# SPv1.net
KiCad netlist of a schematic drawn in EAGLE
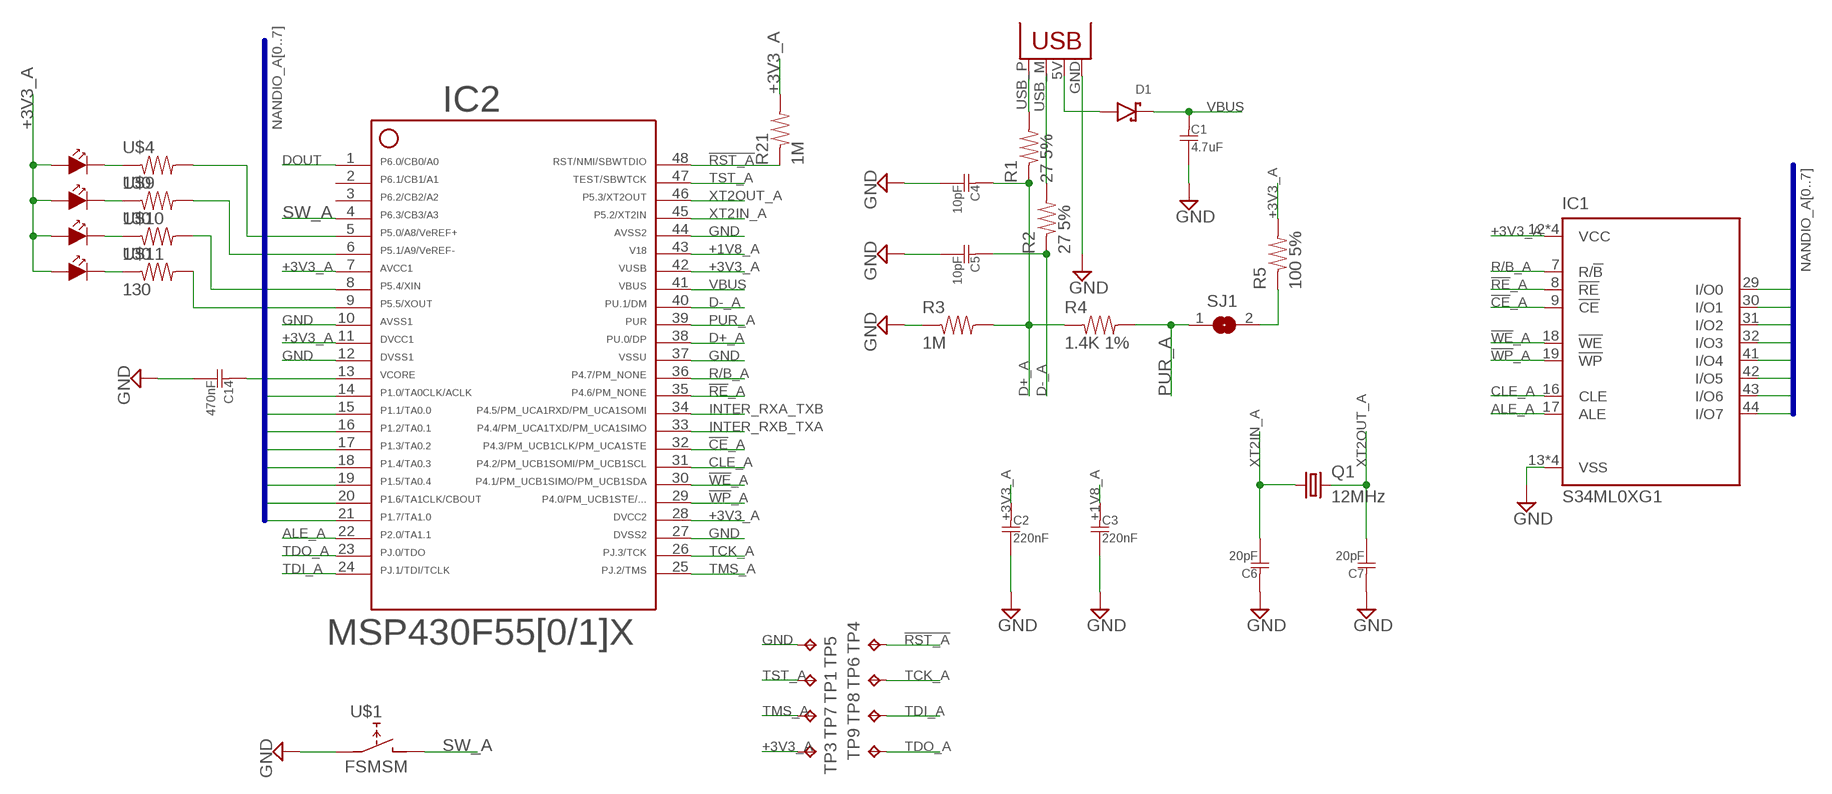
[diagram p0: schematic, sheet 1]
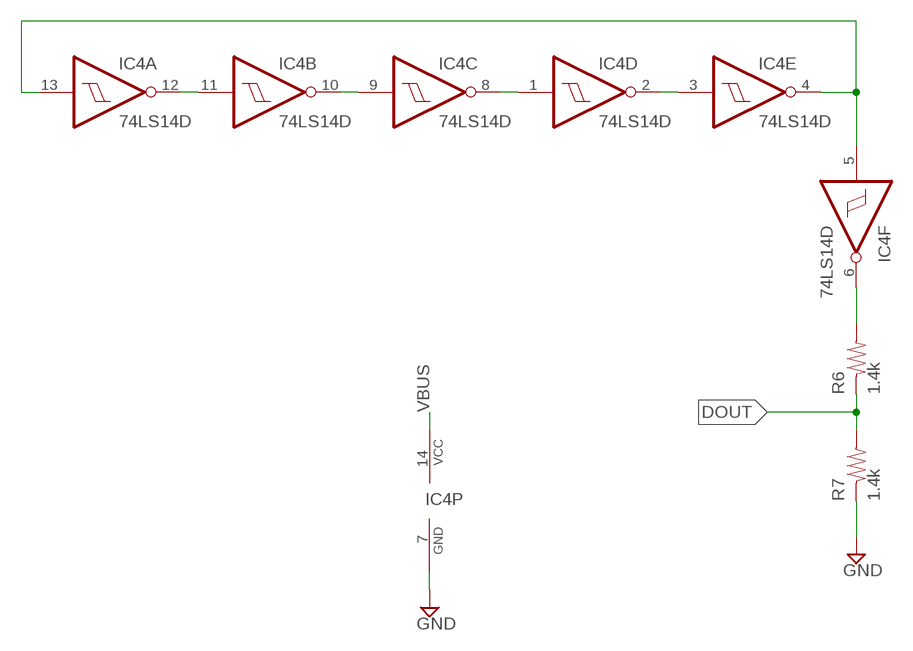
[diagram p1: schematic, sheet 2]
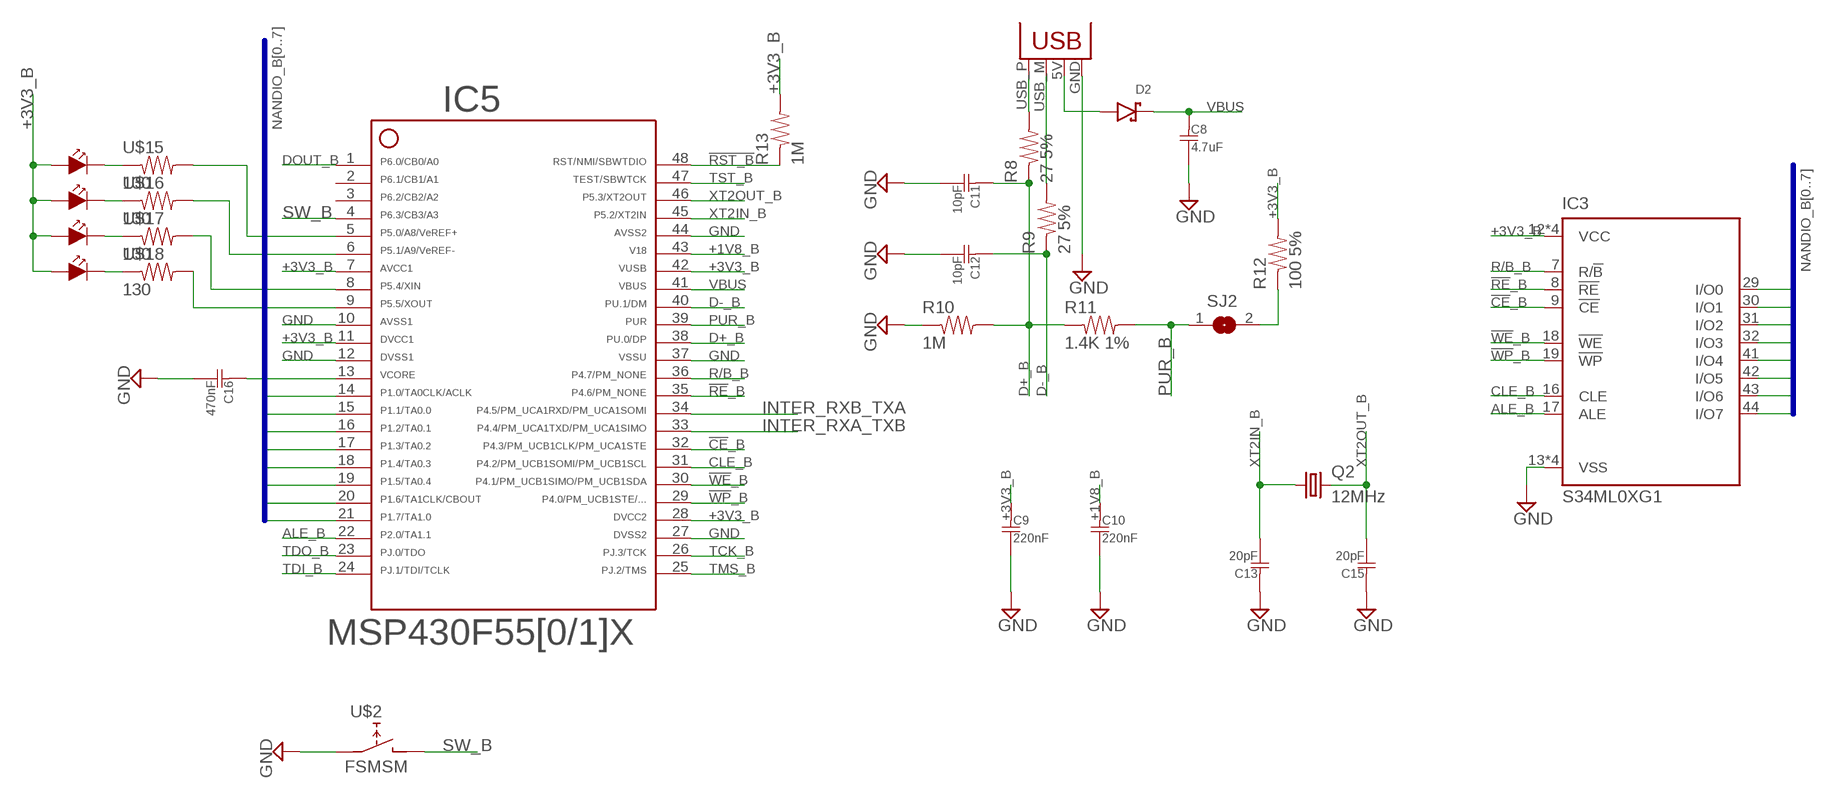
[diagram p2: schematic, sheet 3]
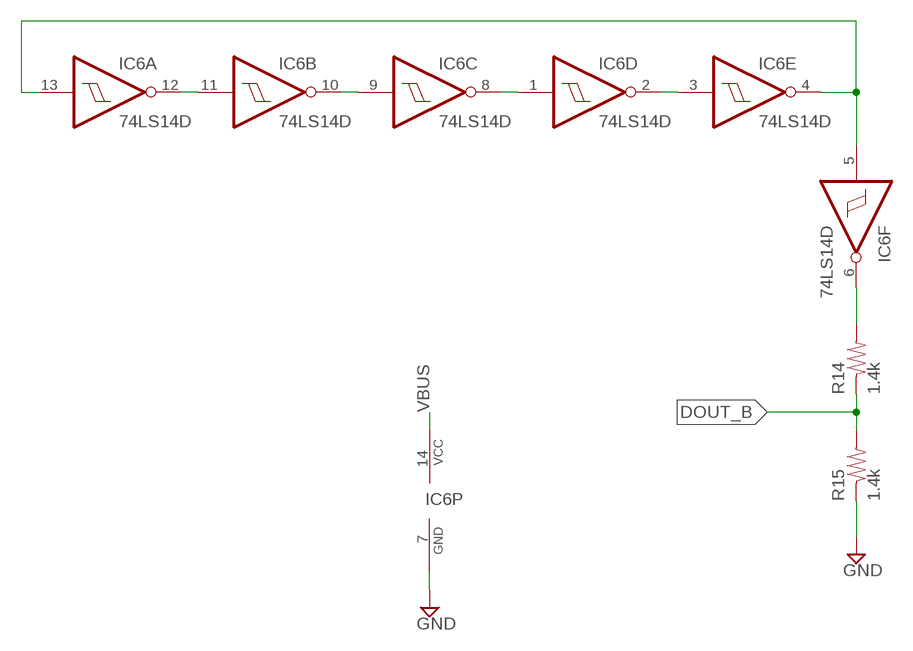
[diagram p3: schematic, sheet 4]

(export (version "E")
  (design (tool "Eeschema 10.0.6"))
  (components
    (comp (ref "IC4")
      (value "74LS14D")
      (footprint "eagle-import:SO14")
      (libsource (lib "eagle-import") (part "7414DLS"))
    )
    (comp (ref "R6")
      (value "1.4k")
      (footprint "eagle-import:R0805")
      (libsource (lib "eagle-import") (part "R0805"))
    )
    (comp (ref "R7")
      (value "1.4k")
      (footprint "eagle-import:R0805")
      (libsource (lib "eagle-import") (part "R0805"))
    )
    (comp (ref "C1")
      (value "4.7uF")
      (footprint "eagle-import:R0805")
      (libsource (lib "eagle-import") (part "C0805"))
    )
    (comp (ref "C2")
      (value "220nF")
      (footprint "eagle-import:R0805")
      (libsource (lib "eagle-import") (part "C0805"))
    )
    (comp (ref "C3")
      (value "220nF")
      (footprint "eagle-import:R0805")
      (libsource (lib "eagle-import") (part "C0805"))
    )
    (comp (ref "C4")
      (value "10pF")
      (footprint "eagle-import:R0805")
      (libsource (lib "eagle-import") (part "C0805"))
    )
    (comp (ref "C5")
      (value "10pF")
      (footprint "eagle-import:R0805")
      (libsource (lib "eagle-import") (part "C0805"))
    )
    (comp (ref "C6")
      (value "20pF")
      (footprint "eagle-import:R0805")
      (libsource (lib "eagle-import") (part "C0805"))
    )
    (comp (ref "C7")
      (value "20pF")
      (footprint "eagle-import:R0805")
      (libsource (lib "eagle-import") (part "C0805"))
    )
    (comp (ref "C14")
      (value "470nF")
      (footprint "eagle-import:R0805")
      (libsource (lib "eagle-import") (part "C0805"))
    )
    (comp (ref "D1")
      (value "D-SCHOTTKY")
      (footprint "eagle-import:SOD123")
      (libsource (lib "eagle-import") (part "D-SCHOTTKY"))
    )
    (comp (ref "IC1")
      (value "S34ML0XG1")
      (footprint "eagle-import:TSOP48")
      (libsource (lib "eagle-import") (part "S34ML0XG1"))
    )
    (comp (ref "IC2")
      (value "F55[0/1]X---PT48")
      (footprint "eagle-import:PT48")
      (libsource (lib "eagle-import") (part "F55[0/1]X---PT48"))
    )
    (comp (ref "JP1")
      (value "USBPCB")
      (footprint "eagle-import:USB-A-PCB")
      (libsource (lib "eagle-import") (part "USBPCB"))
    )
    (comp (ref "Q1")
      (value "12MHz")
      (footprint "eagle-import:CSM-3X")
      (libsource (lib "eagle-import") (part "CRYSTALCSM-3X"))
    )
    (comp (ref "R1")
      (value "27 5%")
      (footprint "eagle-import:R0805")
      (libsource (lib "eagle-import") (part "R0805"))
    )
    (comp (ref "R2")
      (value "27 5%")
      (footprint "eagle-import:R0805")
      (libsource (lib "eagle-import") (part "R0805"))
    )
    (comp (ref "R3")
      (value "1M")
      (footprint "eagle-import:R0805")
      (libsource (lib "eagle-import") (part "R0805"))
    )
    (comp (ref "R4")
      (value "1.4K 1%")
      (footprint "eagle-import:R0805")
      (libsource (lib "eagle-import") (part "R0805"))
    )
    (comp (ref "R5")
      (value "100 5%")
      (footprint "eagle-import:R0805")
      (libsource (lib "eagle-import") (part "R0805"))
    )
    (comp (ref "R21")
      (value "1M")
      (footprint "eagle-import:R0805")
      (libsource (lib "eagle-import") (part "R0805"))
    )
    (comp (ref "SJ1")
      (value "SJW")
      (footprint "eagle-import:SJW")
      (libsource (lib "eagle-import") (part "SJW"))
    )
    (comp (ref "TP1")
      (value "TPTP08SQ")
      (footprint "eagle-import:TP08SQ")
      (libsource (lib "eagle-import") (part "TPTP08SQ"))
    )
    (comp (ref "TP3")
      (value "TPTP08SQ")
      (footprint "eagle-import:TP08SQ")
      (libsource (lib "eagle-import") (part "TPTP08SQ"))
    )
    (comp (ref "TP4")
      (value "TPTP08SQ")
      (footprint "eagle-import:TP08SQ")
      (libsource (lib "eagle-import") (part "TPTP08SQ"))
    )
    (comp (ref "TP5")
      (value "TPTP08SQ")
      (footprint "eagle-import:TP08SQ")
      (libsource (lib "eagle-import") (part "TPTP08SQ"))
    )
    (comp (ref "TP6")
      (value "TPTP08SQ")
      (footprint "eagle-import:TP08SQ")
      (libsource (lib "eagle-import") (part "TPTP08SQ"))
    )
    (comp (ref "TP7")
      (value "TPTP08SQ")
      (footprint "eagle-import:TP08SQ")
      (libsource (lib "eagle-import") (part "TPTP08SQ"))
    )
    (comp (ref "TP8")
      (value "TPTP08SQ")
      (footprint "eagle-import:TP08SQ")
      (libsource (lib "eagle-import") (part "TPTP08SQ"))
    )
    (comp (ref "TP9")
      (value "TPTP08SQ")
      (footprint "eagle-import:TP08SQ")
      (libsource (lib "eagle-import") (part "TPTP08SQ"))
    )
    (comp (ref "U$1")
      (value "FSMSM")
      (footprint "eagle-import:FSMSM")
      (libsource (lib "eagle-import") (part "FSMSM"))
    )
    (comp (ref "U$4")
      (value "130")
      (footprint "eagle-import:R0805")
      (libsource (lib "eagle-import") (part "R0805"))
    )
    (comp (ref "U$5")
      (value "LED")
      (footprint "eagle-import:LED0805")
      (libsource (lib "eagle-import") (part "LED"))
    )
    (comp (ref "U$6")
      (value "LED")
      (footprint "eagle-import:LED0805")
      (libsource (lib "eagle-import") (part "LED"))
    )
    (comp (ref "U$7")
      (value "LED")
      (footprint "eagle-import:LED0805")
      (libsource (lib "eagle-import") (part "LED"))
    )
    (comp (ref "U$8")
      (value "LED")
      (footprint "eagle-import:LED0805")
      (libsource (lib "eagle-import") (part "LED"))
    )
    (comp (ref "U$9")
      (value "130")
      (footprint "eagle-import:R0805")
      (libsource (lib "eagle-import") (part "R0805"))
    )
    (comp (ref "U$10")
      (value "130")
      (footprint "eagle-import:R0805")
      (libsource (lib "eagle-import") (part "R0805"))
    )
    (comp (ref "U$11")
      (value "130")
      (footprint "eagle-import:R0805")
      (libsource (lib "eagle-import") (part "R0805"))
    )
    (comp (ref "C8")
      (value "4.7uF")
      (footprint "eagle-import:R0805")
      (libsource (lib "eagle-import") (part "C0805"))
    )
    (comp (ref "C9")
      (value "220nF")
      (footprint "eagle-import:R0805")
      (libsource (lib "eagle-import") (part "C0805"))
    )
    (comp (ref "C10")
      (value "220nF")
      (footprint "eagle-import:R0805")
      (libsource (lib "eagle-import") (part "C0805"))
    )
    (comp (ref "C11")
      (value "10pF")
      (footprint "eagle-import:R0805")
      (libsource (lib "eagle-import") (part "C0805"))
    )
    (comp (ref "C12")
      (value "10pF")
      (footprint "eagle-import:R0805")
      (libsource (lib "eagle-import") (part "C0805"))
    )
    (comp (ref "C13")
      (value "20pF")
      (footprint "eagle-import:R0805")
      (libsource (lib "eagle-import") (part "C0805"))
    )
    (comp (ref "C15")
      (value "20pF")
      (footprint "eagle-import:R0805")
      (libsource (lib "eagle-import") (part "C0805"))
    )
    (comp (ref "C16")
      (value "470nF")
      (footprint "eagle-import:R0805")
      (libsource (lib "eagle-import") (part "C0805"))
    )
    (comp (ref "D2")
      (value "D-SCHOTTKY")
      (footprint "eagle-import:SOD123")
      (libsource (lib "eagle-import") (part "D-SCHOTTKY"))
    )
    (comp (ref "IC3")
      (value "S34ML0XG1")
      (footprint "eagle-import:TSOP48")
      (libsource (lib "eagle-import") (part "S34ML0XG1"))
    )
    (comp (ref "IC5")
      (value "F55[0/1]X---PT48")
      (footprint "eagle-import:PT48")
      (libsource (lib "eagle-import") (part "F55[0/1]X---PT48"))
    )
    (comp (ref "JP2")
      (value "USBPCB")
      (footprint "eagle-import:USB-A-PCB")
      (libsource (lib "eagle-import") (part "USBPCB"))
    )
    (comp (ref "Q2")
      (value "12MHz")
      (footprint "eagle-import:CSM-3X")
      (libsource (lib "eagle-import") (part "CRYSTALCSM-3X"))
    )
    (comp (ref "R8")
      (value "27 5%")
      (footprint "eagle-import:R0805")
      (libsource (lib "eagle-import") (part "R0805"))
    )
    (comp (ref "R9")
      (value "27 5%")
      (footprint "eagle-import:R0805")
      (libsource (lib "eagle-import") (part "R0805"))
    )
    (comp (ref "R10")
      (value "1M")
      (footprint "eagle-import:R0805")
      (libsource (lib "eagle-import") (part "R0805"))
    )
    (comp (ref "R11")
      (value "1.4K 1%")
      (footprint "eagle-import:R0805")
      (libsource (lib "eagle-import") (part "R0805"))
    )
    (comp (ref "R12")
      (value "100 5%")
      (footprint "eagle-import:R0805")
      (libsource (lib "eagle-import") (part "R0805"))
    )
    (comp (ref "R13")
      (value "1M")
      (footprint "eagle-import:R0805")
      (libsource (lib "eagle-import") (part "R0805"))
    )
    (comp (ref "SJ2")
      (value "SJW")
      (footprint "eagle-import:SJW")
      (libsource (lib "eagle-import") (part "SJW"))
    )
    (comp (ref "U$2")
      (value "FSMSM")
      (footprint "eagle-import:FSMSM")
      (libsource (lib "eagle-import") (part "FSMSM"))
    )
    (comp (ref "U$3")
      (value "LED")
      (footprint "eagle-import:LED0805")
      (libsource (lib "eagle-import") (part "LED"))
    )
    (comp (ref "U$12")
      (value "LED")
      (footprint "eagle-import:LED0805")
      (libsource (lib "eagle-import") (part "LED"))
    )
    (comp (ref "U$13")
      (value "LED")
      (footprint "eagle-import:LED0805")
      (libsource (lib "eagle-import") (part "LED"))
    )
    (comp (ref "U$14")
      (value "LED")
      (footprint "eagle-import:LED0805")
      (libsource (lib "eagle-import") (part "LED"))
    )
    (comp (ref "U$15")
      (value "130")
      (footprint "eagle-import:R0805")
      (libsource (lib "eagle-import") (part "R0805"))
    )
    (comp (ref "U$16")
      (value "130")
      (footprint "eagle-import:R0805")
      (libsource (lib "eagle-import") (part "R0805"))
    )
    (comp (ref "U$17")
      (value "130")
      (footprint "eagle-import:R0805")
      (libsource (lib "eagle-import") (part "R0805"))
    )
    (comp (ref "U$18")
      (value "130")
      (footprint "eagle-import:R0805")
      (libsource (lib "eagle-import") (part "R0805"))
    )
    (comp (ref "IC6")
      (value "74LS14D")
      (footprint "eagle-import:SO14")
      (libsource (lib "eagle-import") (part "7414DLS"))
    )
    (comp (ref "R14")
      (value "1.4k")
      (footprint "eagle-import:R0805")
      (libsource (lib "eagle-import") (part "R0805"))
    )
    (comp (ref "R15")
      (value "1.4k")
      (footprint "eagle-import:R0805")
      (libsource (lib "eagle-import") (part "R0805"))
    )
  )
  (nets
    (net (code "9") (name "+1V8_A") (class "Default")
      (node (ref "C3") (pin "P$1") (pinfunction "1_P$1") (pintype "passive"))
      (node (ref "IC2") (pin "43") (pinfunction "43_43") (pintype "power_in"))
    )
    (net (code "10") (name "+1V8_B") (class "Default")
      (node (ref "C10") (pin "P$1") (pinfunction "1_P$1") (pintype "passive"))
      (node (ref "IC5") (pin "43") (pinfunction "43_43") (pintype "power_in"))
    )
    (net (code "11") (name "+3V3_A") (class "Default")
      (node (ref "C2") (pin "P$1") (pinfunction "1_P$1") (pintype "passive"))
      (node (ref "IC1") (pin "12") (pinfunction "VCC_12") (pintype "power_in"))
      (node (ref "IC1") (pin "34") (pinfunction "VCC_34") (pintype "power_in"))
      (node (ref "IC1") (pin "37") (pinfunction "VCC_37") (pintype "power_in"))
      (node (ref "IC1") (pin "39") (pinfunction "VCC_39") (pintype "power_in"))
      (node (ref "IC2") (pin "11") (pinfunction "11_11") (pintype "power_in"))
      (node (ref "IC2") (pin "28") (pinfunction "28_28") (pintype "power_in"))
      (node (ref "IC2") (pin "42") (pinfunction "42_42") (pintype "power_in"))
      (node (ref "IC2") (pin "7") (pinfunction "7_7") (pintype "power_in"))
      (node (ref "R21") (pin "P$2") (pinfunction "2_P$2") (pintype "passive"))
      (node (ref "R5") (pin "P$2") (pinfunction "2_P$2") (pintype "passive"))
      (node (ref "TP3") (pin "TP") (pinfunction "TP_TP") (pintype "input"))
      (node (ref "U$5") (pin "ANODE") (pinfunction "ANODE_ANODE") (pintype "passive"))
      (node (ref "U$6") (pin "ANODE") (pinfunction "ANODE_ANODE") (pintype "passive"))
      (node (ref "U$7") (pin "ANODE") (pinfunction "ANODE_ANODE") (pintype "passive"))
      (node (ref "U$8") (pin "ANODE") (pinfunction "ANODE_ANODE") (pintype "passive"))
    )
    (net (code "12") (name "+3V3_B") (class "Default")
      (node (ref "C9") (pin "P$1") (pinfunction "1_P$1") (pintype "passive"))
      (node (ref "IC3") (pin "12") (pinfunction "VCC_12") (pintype "power_in"))
      (node (ref "IC3") (pin "34") (pinfunction "VCC_34") (pintype "power_in"))
      (node (ref "IC3") (pin "37") (pinfunction "VCC_37") (pintype "power_in"))
      (node (ref "IC3") (pin "39") (pinfunction "VCC_39") (pintype "power_in"))
      (node (ref "IC5") (pin "11") (pinfunction "11_11") (pintype "power_in"))
      (node (ref "IC5") (pin "28") (pinfunction "28_28") (pintype "power_in"))
      (node (ref "IC5") (pin "42") (pinfunction "42_42") (pintype "power_in"))
      (node (ref "IC5") (pin "7") (pinfunction "7_7") (pintype "power_in"))
      (node (ref "R12") (pin "P$2") (pinfunction "2_P$2") (pintype "passive"))
      (node (ref "R13") (pin "P$2") (pinfunction "2_P$2") (pintype "passive"))
      (node (ref "U$12") (pin "ANODE") (pinfunction "ANODE_ANODE") (pintype "passive"))
      (node (ref "U$13") (pin "ANODE") (pinfunction "ANODE_ANODE") (pintype "passive"))
      (node (ref "U$14") (pin "ANODE") (pinfunction "ANODE_ANODE") (pintype "passive"))
      (node (ref "U$3") (pin "ANODE") (pinfunction "ANODE_ANODE") (pintype "passive"))
    )
    (net (code "15") (name "ALE_A") (class "Default")
      (node (ref "IC1") (pin "17") (pinfunction "ALE_17") (pintype "input"))
      (node (ref "IC2") (pin "22") (pinfunction "22_22") (pintype "bidirectional"))
    )
    (net (code "16") (name "ALE_B") (class "Default")
      (node (ref "IC3") (pin "17") (pinfunction "ALE_17") (pintype "input"))
      (node (ref "IC5") (pin "22") (pinfunction "22_22") (pintype "bidirectional"))
    )
    (net (code "17") (name "CLE_A") (class "Default")
      (node (ref "IC1") (pin "16") (pinfunction "CLE_16") (pintype "input"))
      (node (ref "IC2") (pin "31") (pinfunction "31_31") (pintype "bidirectional"))
    )
    (net (code "18") (name "CLE_B") (class "Default")
      (node (ref "IC3") (pin "16") (pinfunction "CLE_16") (pintype "input"))
      (node (ref "IC5") (pin "31") (pinfunction "31_31") (pintype "bidirectional"))
    )
    (net (code "19") (name "D+_A") (class "Default")
      (node (ref "C4") (pin "P$1") (pinfunction "1_P$1") (pintype "passive"))
      (node (ref "IC2") (pin "38") (pinfunction "38_38") (pintype "bidirectional"))
      (node (ref "R1") (pin "P$1") (pinfunction "1_P$1") (pintype "passive"))
      (node (ref "R3") (pin "P$2") (pinfunction "2_P$2") (pintype "passive"))
      (node (ref "R4") (pin "P$1") (pinfunction "1_P$1") (pintype "passive"))
    )
    (net (code "20") (name "D+_B") (class "Default")
      (node (ref "C11") (pin "P$1") (pinfunction "1_P$1") (pintype "passive"))
      (node (ref "IC5") (pin "38") (pinfunction "38_38") (pintype "bidirectional"))
      (node (ref "R10") (pin "P$2") (pinfunction "2_P$2") (pintype "passive"))
      (node (ref "R11") (pin "P$1") (pinfunction "1_P$1") (pintype "passive"))
      (node (ref "R8") (pin "P$1") (pinfunction "1_P$1") (pintype "passive"))
    )
    (net (code "21") (name "D-_A") (class "Default")
      (node (ref "C5") (pin "P$1") (pinfunction "1_P$1") (pintype "passive"))
      (node (ref "IC2") (pin "40") (pinfunction "40_40") (pintype "bidirectional"))
      (node (ref "R2") (pin "P$1") (pinfunction "1_P$1") (pintype "passive"))
    )
    (net (code "22") (name "D-_B") (class "Default")
      (node (ref "C12") (pin "P$1") (pinfunction "1_P$1") (pintype "passive"))
      (node (ref "IC5") (pin "40") (pinfunction "40_40") (pintype "bidirectional"))
      (node (ref "R9") (pin "P$1") (pinfunction "1_P$1") (pintype "passive"))
    )
    (net (code "23") (name "DOUT") (class "Default")
      (node (ref "IC2") (pin "1") (pinfunction "1_1") (pintype "bidirectional"))
      (node (ref "R6") (pin "P$1") (pinfunction "1_P$1") (pintype "passive"))
      (node (ref "R7") (pin "P$2") (pinfunction "2_P$2") (pintype "passive"))
    )
    (net (code "24") (name "DOUT_B") (class "Default")
      (node (ref "IC5") (pin "1") (pinfunction "1_1") (pintype "bidirectional"))
      (node (ref "R14") (pin "P$1") (pinfunction "1_P$1") (pintype "passive"))
      (node (ref "R15") (pin "P$2") (pinfunction "2_P$2") (pintype "passive"))
    )
    (net (code "25") (name "GND") (class "Default")
      (node (ref "C1") (pin "P$2") (pinfunction "2_P$2") (pintype "passive"))
      (node (ref "C10") (pin "P$2") (pinfunction "2_P$2") (pintype "passive"))
      (node (ref "C11") (pin "P$2") (pinfunction "2_P$2") (pintype "passive"))
      (node (ref "C12") (pin "P$2") (pinfunction "2_P$2") (pintype "passive"))
      (node (ref "C13") (pin "P$1") (pinfunction "1_P$1") (pintype "passive"))
      (node (ref "C14") (pin "P$2") (pinfunction "2_P$2") (pintype "passive"))
      (node (ref "C15") (pin "P$1") (pinfunction "1_P$1") (pintype "passive"))
      (node (ref "C16") (pin "P$2") (pinfunction "2_P$2") (pintype "passive"))
      (node (ref "C2") (pin "P$2") (pinfunction "2_P$2") (pintype "passive"))
      (node (ref "C3") (pin "P$2") (pinfunction "2_P$2") (pintype "passive"))
      (node (ref "C4") (pin "P$2") (pinfunction "2_P$2") (pintype "passive"))
      (node (ref "C5") (pin "P$2") (pinfunction "2_P$2") (pintype "passive"))
      (node (ref "C6") (pin "P$1") (pinfunction "1_P$1") (pintype "passive"))
      (node (ref "C7") (pin "P$1") (pinfunction "1_P$1") (pintype "passive"))
      (node (ref "C8") (pin "P$2") (pinfunction "2_P$2") (pintype "passive"))
      (node (ref "C9") (pin "P$2") (pinfunction "2_P$2") (pintype "passive"))
      (node (ref "IC1") (pin "13") (pinfunction "VSS_13") (pintype "power_in"))
      (node (ref "IC1") (pin "25") (pinfunction "VSS_25") (pintype "power_in"))
      (node (ref "IC1") (pin "36") (pinfunction "VSS_36") (pintype "power_in"))
      (node (ref "IC1") (pin "48") (pinfunction "VSS_48") (pintype "power_in"))
      (node (ref "IC2") (pin "10") (pinfunction "10_10") (pintype "power_in"))
      (node (ref "IC2") (pin "12") (pinfunction "12_12") (pintype "power_in"))
      (node (ref "IC2") (pin "27") (pinfunction "27_27") (pintype "power_in"))
      (node (ref "IC2") (pin "37") (pinfunction "37_37") (pintype "power_in"))
      (node (ref "IC2") (pin "44") (pinfunction "44_44") (pintype "power_in"))
      (node (ref "IC3") (pin "13") (pinfunction "VSS_13") (pintype "power_in"))
      (node (ref "IC3") (pin "25") (pinfunction "VSS_25") (pintype "power_in"))
      (node (ref "IC3") (pin "36") (pinfunction "VSS_36") (pintype "power_in"))
      (node (ref "IC3") (pin "48") (pinfunction "VSS_48") (pintype "power_in"))
      (node (ref "IC4") (pin "7") (pinfunction "GND_7") (pintype "power_in"))
      (node (ref "IC5") (pin "10") (pinfunction "10_10") (pintype "power_in"))
      (node (ref "IC5") (pin "12") (pinfunction "12_12") (pintype "power_in"))
      (node (ref "IC5") (pin "27") (pinfunction "27_27") (pintype "power_in"))
      (node (ref "IC5") (pin "37") (pinfunction "37_37") (pintype "power_in"))
      (node (ref "IC5") (pin "44") (pinfunction "44_44") (pintype "power_in"))
      (node (ref "IC6") (pin "7") (pinfunction "GND_7") (pintype "power_in"))
      (node (ref "JP1") (pin "GND") (pinfunction "GND_GND") (pintype "bidirectional"))
      (node (ref "JP2") (pin "GND") (pinfunction "GND_GND") (pintype "bidirectional"))
      (node (ref "R10") (pin "P$1") (pinfunction "1_P$1") (pintype "passive"))
      (node (ref "R15") (pin "P$1") (pinfunction "1_P$1") (pintype "passive"))
      (node (ref "R3") (pin "P$1") (pinfunction "1_P$1") (pintype "passive"))
      (node (ref "R7") (pin "P$1") (pinfunction "1_P$1") (pintype "passive"))
      (node (ref "TP5") (pin "TP") (pinfunction "TP_TP") (pintype "input"))
      (node (ref "U$1") (pin "P$1") (pinfunction "A1_P$1") (pintype "passive"))
      (node (ref "U$2") (pin "P$1") (pinfunction "A1_P$1") (pintype "passive"))
    )
    (net (code "26") (name "INTER_RXA_TXB") (class "Default")
      (node (ref "IC2") (pin "34") (pinfunction "34_34") (pintype "bidirectional"))
      (node (ref "IC5") (pin "33") (pinfunction "33_33") (pintype "bidirectional"))
    )
    (net (code "27") (name "INTER_RXB_TXA") (class "Default")
      (node (ref "IC2") (pin "33") (pinfunction "33_33") (pintype "bidirectional"))
      (node (ref "IC5") (pin "34") (pinfunction "34_34") (pintype "bidirectional"))
    )
    (net (code "28") (name "NANDIO_A0") (class "Default")
      (node (ref "IC1") (pin "29") (pinfunction "I/O0_29") (pintype "bidirectional"))
      (node (ref "IC2") (pin "14") (pinfunction "14_14") (pintype "bidirectional"))
    )
    (net (code "29") (name "NANDIO_A1") (class "Default")
      (node (ref "IC1") (pin "30") (pinfunction "I/O1_30") (pintype "bidirectional"))
      (node (ref "IC2") (pin "15") (pinfunction "15_15") (pintype "bidirectional"))
    )
    (net (code "30") (name "NANDIO_A2") (class "Default")
      (node (ref "IC1") (pin "31") (pinfunction "I/O2_31") (pintype "bidirectional"))
      (node (ref "IC2") (pin "16") (pinfunction "16_16") (pintype "bidirectional"))
    )
    (net (code "31") (name "NANDIO_A3") (class "Default")
      (node (ref "IC1") (pin "32") (pinfunction "I/O3_32") (pintype "bidirectional"))
      (node (ref "IC2") (pin "17") (pinfunction "17_17") (pintype "bidirectional"))
    )
    (net (code "32") (name "NANDIO_A4") (class "Default")
      (node (ref "IC1") (pin "41") (pinfunction "I/O4_41") (pintype "bidirectional"))
      (node (ref "IC2") (pin "18") (pinfunction "18_18") (pintype "bidirectional"))
    )
    (net (code "33") (name "NANDIO_A5") (class "Default")
      (node (ref "IC1") (pin "42") (pinfunction "I/O5_42") (pintype "bidirectional"))
      (node (ref "IC2") (pin "19") (pinfunction "19_19") (pintype "bidirectional"))
    )
    (net (code "34") (name "NANDIO_A6") (class "Default")
      (node (ref "IC1") (pin "43") (pinfunction "I/O6_43") (pintype "bidirectional"))
      (node (ref "IC2") (pin "20") (pinfunction "20_20") (pintype "bidirectional"))
    )
    (net (code "35") (name "NANDIO_A7") (class "Default")
      (node (ref "IC1") (pin "44") (pinfunction "I/O7_44") (pintype "bidirectional"))
      (node (ref "IC2") (pin "21") (pinfunction "21_21") (pintype "bidirectional"))
    )
    (net (code "36") (name "NANDIO_A8") (class "Default")
      (node (ref "IC3") (pin "29") (pinfunction "I/O0_29") (pintype "bidirectional"))
      (node (ref "IC5") (pin "14") (pinfunction "14_14") (pintype "bidirectional"))
    )
    (net (code "37") (name "NANDIO_A9") (class "Default")
      (node (ref "IC3") (pin "30") (pinfunction "I/O1_30") (pintype "bidirectional"))
      (node (ref "IC5") (pin "15") (pinfunction "15_15") (pintype "bidirectional"))
    )
    (net (code "38") (name "NANDIO_A10") (class "Default")
      (node (ref "IC3") (pin "31") (pinfunction "I/O2_31") (pintype "bidirectional"))
      (node (ref "IC5") (pin "16") (pinfunction "16_16") (pintype "bidirectional"))
    )
    (net (code "39") (name "NANDIO_A11") (class "Default")
      (node (ref "IC3") (pin "32") (pinfunction "I/O3_32") (pintype "bidirectional"))
      (node (ref "IC5") (pin "17") (pinfunction "17_17") (pintype "bidirectional"))
    )
    (net (code "40") (name "NANDIO_A12") (class "Default")
      (node (ref "IC3") (pin "41") (pinfunction "I/O4_41") (pintype "bidirectional"))
      (node (ref "IC5") (pin "18") (pinfunction "18_18") (pintype "bidirectional"))
    )
    (net (code "41") (name "NANDIO_A13") (class "Default")
      (node (ref "IC3") (pin "42") (pinfunction "I/O5_42") (pintype "bidirectional"))
      (node (ref "IC5") (pin "19") (pinfunction "19_19") (pintype "bidirectional"))
    )
    (net (code "42") (name "NANDIO_A14") (class "Default")
      (node (ref "IC3") (pin "43") (pinfunction "I/O6_43") (pintype "bidirectional"))
      (node (ref "IC5") (pin "20") (pinfunction "20_20") (pintype "bidirectional"))
    )
    (net (code "43") (name "NANDIO_A15") (class "Default")
      (node (ref "IC3") (pin "44") (pinfunction "I/O7_44") (pintype "bidirectional"))
      (node (ref "IC5") (pin "21") (pinfunction "21_21") (pintype "bidirectional"))
    )
    (net (code "44") (name "Net-(C14-1)") (class "Default")
      (node (ref "C14") (pin "P$1") (pinfunction "1_P$1") (pintype "passive"))
      (node (ref "IC2") (pin "13") (pinfunction "13_13") (pintype "power_in"))
    )
    (net (code "45") (name "Net-(C16-1)") (class "Default")
      (node (ref "C16") (pin "P$1") (pinfunction "1_P$1") (pintype "passive"))
      (node (ref "IC5") (pin "13") (pinfunction "13_13") (pintype "power_in"))
    )
    (net (code "46") (name "Net-(IC4A-I)") (class "Default")
      (node (ref "IC4") (pin "13") (pinfunction "I_13") (pintype "input"))
      (node (ref "IC4") (pin "4") (pinfunction "O_4") (pintype "output"))
      (node (ref "IC4") (pin "5") (pinfunction "I_5") (pintype "input"))
    )
    (net (code "47") (name "Net-(IC4A-O)") (class "Default")
      (node (ref "IC4") (pin "11") (pinfunction "I_11") (pintype "input"))
      (node (ref "IC4") (pin "12") (pinfunction "O_12") (pintype "output"))
    )
    (net (code "48") (name "Net-(IC4B-O)") (class "Default")
      (node (ref "IC4") (pin "10") (pinfunction "O_10") (pintype "output"))
      (node (ref "IC4") (pin "9") (pinfunction "I_9") (pintype "input"))
    )
    (net (code "49") (name "Net-(IC4C-O)") (class "Default")
      (node (ref "IC4") (pin "1") (pinfunction "I_1") (pintype "input"))
      (node (ref "IC4") (pin "8") (pinfunction "O_8") (pintype "output"))
    )
    (net (code "50") (name "Net-(IC4D-O)") (class "Default")
      (node (ref "IC4") (pin "2") (pinfunction "O_2") (pintype "output"))
      (node (ref "IC4") (pin "3") (pinfunction "I_3") (pintype "input"))
    )
    (net (code "51") (name "Net-(IC4F-O)") (class "Default")
      (node (ref "IC4") (pin "6") (pinfunction "O_6") (pintype "output"))
      (node (ref "R6") (pin "P$2") (pinfunction "2_P$2") (pintype "passive"))
    )
    (net (code "52") (name "Net-(IC6A-I)") (class "Default")
      (node (ref "IC6") (pin "13") (pinfunction "I_13") (pintype "input"))
      (node (ref "IC6") (pin "4") (pinfunction "O_4") (pintype "output"))
      (node (ref "IC6") (pin "5") (pinfunction "I_5") (pintype "input"))
    )
    (net (code "53") (name "Net-(IC6A-O)") (class "Default")
      (node (ref "IC6") (pin "11") (pinfunction "I_11") (pintype "input"))
      (node (ref "IC6") (pin "12") (pinfunction "O_12") (pintype "output"))
    )
    (net (code "54") (name "Net-(IC6B-O)") (class "Default")
      (node (ref "IC6") (pin "10") (pinfunction "O_10") (pintype "output"))
      (node (ref "IC6") (pin "9") (pinfunction "I_9") (pintype "input"))
    )
    (net (code "55") (name "Net-(IC6C-O)") (class "Default")
      (node (ref "IC6") (pin "1") (pinfunction "I_1") (pintype "input"))
      (node (ref "IC6") (pin "8") (pinfunction "O_8") (pintype "output"))
    )
    (net (code "56") (name "Net-(IC6D-O)") (class "Default")
      (node (ref "IC6") (pin "2") (pinfunction "O_2") (pintype "output"))
      (node (ref "IC6") (pin "3") (pinfunction "I_3") (pintype "input"))
    )
    (net (code "57") (name "Net-(IC6F-O)") (class "Default")
      (node (ref "IC6") (pin "6") (pinfunction "O_6") (pintype "output"))
      (node (ref "R14") (pin "P$2") (pinfunction "2_P$2") (pintype "passive"))
    )
    (net (code "58") (name "Net-(JP1-D+)") (class "Default")
      (node (ref "JP1") (pin "USB_P") (pinfunction "D+_USB_P") (pintype "bidirectional"))
      (node (ref "R1") (pin "P$2") (pinfunction "2_P$2") (pintype "passive"))
    )
    (net (code "59") (name "Net-(JP1-D-)") (class "Default")
      (node (ref "JP1") (pin "USB_M") (pinfunction "D-_USB_M") (pintype "bidirectional"))
      (node (ref "R2") (pin "P$2") (pinfunction "2_P$2") (pintype "passive"))
    )
    (net (code "60") (name "Net-(JP1-VBUS)") (class "Default")
      (node (ref "D1") (pin "ANODE") (pinfunction "ANODE_ANODE") (pintype "passive"))
      (node (ref "JP1") (pin "5V") (pinfunction "VBUS_5V") (pintype "bidirectional"))
    )
    (net (code "61") (name "Net-(JP2-D+)") (class "Default")
      (node (ref "JP2") (pin "USB_P") (pinfunction "D+_USB_P") (pintype "bidirectional"))
      (node (ref "R8") (pin "P$2") (pinfunction "2_P$2") (pintype "passive"))
    )
    (net (code "62") (name "Net-(JP2-D-)") (class "Default")
      (node (ref "JP2") (pin "USB_M") (pinfunction "D-_USB_M") (pintype "bidirectional"))
      (node (ref "R9") (pin "P$2") (pinfunction "2_P$2") (pintype "passive"))
    )
    (net (code "63") (name "Net-(JP2-VBUS)") (class "Default")
      (node (ref "D2") (pin "ANODE") (pinfunction "ANODE_ANODE") (pintype "passive"))
      (node (ref "JP2") (pin "5V") (pinfunction "VBUS_5V") (pintype "bidirectional"))
    )
    (net (code "64") (name "Net-(R5-1)") (class "Default")
      (node (ref "R5") (pin "P$1") (pinfunction "1_P$1") (pintype "passive"))
      (node (ref "SJ1") (pin "2") (pinfunction "2_2") (pintype "passive"))
    )
    (net (code "65") (name "Net-(R12-1)") (class "Default")
      (node (ref "R12") (pin "P$1") (pinfunction "1_P$1") (pintype "passive"))
      (node (ref "SJ2") (pin "2") (pinfunction "2_2") (pintype "passive"))
    )
    (net (code "66") (name "Net-(U$4-1)") (class "Default")
      (node (ref "U$4") (pin "P$1") (pinfunction "1_P$1") (pintype "passive"))
      (node (ref "U$5") (pin "CATHODE") (pinfunction "CATHODE_CATHODE") (pintype "passive"))
    )
    (net (code "67") (name "Net-(U$4-2)") (class "Default")
      (node (ref "IC2") (pin "5") (pinfunction "5_5") (pintype "bidirectional"))
      (node (ref "U$4") (pin "P$2") (pinfunction "2_P$2") (pintype "passive"))
    )
    (net (code "68") (name "Net-(U$9-1)") (class "Default")
      (node (ref "U$6") (pin "CATHODE") (pinfunction "CATHODE_CATHODE") (pintype "passive"))
      (node (ref "U$9") (pin "P$1") (pinfunction "1_P$1") (pintype "passive"))
    )
    (net (code "69") (name "Net-(U$9-2)") (class "Default")
      (node (ref "IC2") (pin "6") (pinfunction "6_6") (pintype "bidirectional"))
      (node (ref "U$9") (pin "P$2") (pinfunction "2_P$2") (pintype "passive"))
    )
    (net (code "70") (name "Net-(U$10-1)") (class "Default")
      (node (ref "U$10") (pin "P$1") (pinfunction "1_P$1") (pintype "passive"))
      (node (ref "U$7") (pin "CATHODE") (pinfunction "CATHODE_CATHODE") (pintype "passive"))
    )
    (net (code "71") (name "Net-(U$10-2)") (class "Default")
      (node (ref "IC2") (pin "8") (pinfunction "8_8") (pintype "bidirectional"))
      (node (ref "U$10") (pin "P$2") (pinfunction "2_P$2") (pintype "passive"))
    )
    (net (code "72") (name "Net-(U$11-1)") (class "Default")
      (node (ref "U$11") (pin "P$1") (pinfunction "1_P$1") (pintype "passive"))
      (node (ref "U$8") (pin "CATHODE") (pinfunction "CATHODE_CATHODE") (pintype "passive"))
    )
    (net (code "73") (name "Net-(U$11-2)") (class "Default")
      (node (ref "IC2") (pin "9") (pinfunction "9_9") (pintype "bidirectional"))
      (node (ref "U$11") (pin "P$2") (pinfunction "2_P$2") (pintype "passive"))
    )
    (net (code "74") (name "Net-(U$15-1)") (class "Default")
      (node (ref "U$15") (pin "P$1") (pinfunction "1_P$1") (pintype "passive"))
      (node (ref "U$3") (pin "CATHODE") (pinfunction "CATHODE_CATHODE") (pintype "passive"))
    )
    (net (code "75") (name "Net-(U$15-2)") (class "Default")
      (node (ref "IC5") (pin "5") (pinfunction "5_5") (pintype "bidirectional"))
      (node (ref "U$15") (pin "P$2") (pinfunction "2_P$2") (pintype "passive"))
    )
    (net (code "76") (name "Net-(U$16-1)") (class "Default")
      (node (ref "U$12") (pin "CATHODE") (pinfunction "CATHODE_CATHODE") (pintype "passive"))
      (node (ref "U$16") (pin "P$1") (pinfunction "1_P$1") (pintype "passive"))
    )
    (net (code "77") (name "Net-(U$16-2)") (class "Default")
      (node (ref "IC5") (pin "6") (pinfunction "6_6") (pintype "bidirectional"))
      (node (ref "U$16") (pin "P$2") (pinfunction "2_P$2") (pintype "passive"))
    )
    (net (code "78") (name "Net-(U$17-1)") (class "Default")
      (node (ref "U$13") (pin "CATHODE") (pinfunction "CATHODE_CATHODE") (pintype "passive"))
      (node (ref "U$17") (pin "P$1") (pinfunction "1_P$1") (pintype "passive"))
    )
    (net (code "79") (name "Net-(U$17-2)") (class "Default")
      (node (ref "IC5") (pin "8") (pinfunction "8_8") (pintype "bidirectional"))
      (node (ref "U$17") (pin "P$2") (pinfunction "2_P$2") (pintype "passive"))
    )
    (net (code "80") (name "Net-(U$18-1)") (class "Default")
      (node (ref "U$14") (pin "CATHODE") (pinfunction "CATHODE_CATHODE") (pintype "passive"))
      (node (ref "U$18") (pin "P$1") (pinfunction "1_P$1") (pintype "passive"))
    )
    (net (code "81") (name "Net-(U$18-2)") (class "Default")
      (node (ref "IC5") (pin "9") (pinfunction "9_9") (pintype "bidirectional"))
      (node (ref "U$18") (pin "P$2") (pinfunction "2_P$2") (pintype "passive"))
    )
    (net (code "82") (name "PUR_A") (class "Default")
      (node (ref "IC2") (pin "39") (pinfunction "39_39") (pintype "bidirectional"))
      (node (ref "R4") (pin "P$2") (pinfunction "2_P$2") (pintype "passive"))
      (node (ref "SJ1") (pin "1") (pinfunction "1_1") (pintype "passive"))
    )
    (net (code "83") (name "PUR_B") (class "Default")
      (node (ref "IC5") (pin "39") (pinfunction "39_39") (pintype "bidirectional"))
      (node (ref "R11") (pin "P$2") (pinfunction "2_P$2") (pintype "passive"))
      (node (ref "SJ2") (pin "1") (pinfunction "1_1") (pintype "passive"))
    )
    (net (code "84") (name "R{slash}B_A") (class "Default")
      (node (ref "IC1") (pin "7") (pinfunction "R/~{B}_7") (pintype "input"))
      (node (ref "IC2") (pin "36") (pinfunction "36_36") (pintype "bidirectional"))
    )
    (net (code "85") (name "R{slash}B_B") (class "Default")
      (node (ref "IC3") (pin "7") (pinfunction "R/~{B}_7") (pintype "input"))
      (node (ref "IC5") (pin "36") (pinfunction "36_36") (pintype "bidirectional"))
    )
    (net (code "86") (name "SW_A") (class "Default")
      (node (ref "IC2") (pin "4") (pinfunction "4_4") (pintype "bidirectional"))
      (node (ref "U$1") (pin "P$2") (pinfunction "B_P$2") (pintype "passive"))
    )
    (net (code "87") (name "SW_B") (class "Default")
      (node (ref "IC5") (pin "4") (pinfunction "4_4") (pintype "bidirectional"))
      (node (ref "U$2") (pin "P$2") (pinfunction "B_P$2") (pintype "passive"))
    )
    (net (code "88") (name "TCK_A") (class "Default")
      (node (ref "IC2") (pin "26") (pinfunction "26_26") (pintype "bidirectional"))
      (node (ref "TP6") (pin "TP") (pinfunction "TP_TP") (pintype "input"))
    )
    (net (code "89") (name "TCK_B") (class "Default")
      (node (ref "IC5") (pin "26") (pinfunction "26_26") (pintype "bidirectional"))
    )
    (net (code "90") (name "TDI_A") (class "Default")
      (node (ref "IC2") (pin "24") (pinfunction "24_24") (pintype "bidirectional"))
      (node (ref "TP8") (pin "TP") (pinfunction "TP_TP") (pintype "input"))
    )
    (net (code "91") (name "TDI_B") (class "Default")
      (node (ref "IC5") (pin "24") (pinfunction "24_24") (pintype "bidirectional"))
    )
    (net (code "92") (name "TDO_A") (class "Default")
      (node (ref "IC2") (pin "23") (pinfunction "23_23") (pintype "bidirectional"))
      (node (ref "TP9") (pin "TP") (pinfunction "TP_TP") (pintype "input"))
    )
    (net (code "93") (name "TDO_B") (class "Default")
      (node (ref "IC5") (pin "23") (pinfunction "23_23") (pintype "bidirectional"))
    )
    (net (code "94") (name "TMS_A") (class "Default")
      (node (ref "IC2") (pin "25") (pinfunction "25_25") (pintype "bidirectional"))
      (node (ref "TP7") (pin "TP") (pinfunction "TP_TP") (pintype "input"))
    )
    (net (code "95") (name "TMS_B") (class "Default")
      (node (ref "IC5") (pin "25") (pinfunction "25_25") (pintype "bidirectional"))
    )
    (net (code "96") (name "TST_A") (class "Default")
      (node (ref "IC2") (pin "47") (pinfunction "47_47") (pintype "input"))
      (node (ref "TP1") (pin "TP") (pinfunction "TP_TP") (pintype "input"))
    )
    (net (code "97") (name "TST_B") (class "Default")
      (node (ref "IC5") (pin "47") (pinfunction "47_47") (pintype "input"))
    )
    (net (code "98") (name "VBUS") (class "Default")
      (node (ref "C1") (pin "P$1") (pinfunction "1_P$1") (pintype "passive"))
      (node (ref "C8") (pin "P$1") (pinfunction "1_P$1") (pintype "passive"))
      (node (ref "D1") (pin "CATHODE") (pinfunction "CATHODE_CATHODE") (pintype "passive"))
      (node (ref "D2") (pin "CATHODE") (pinfunction "CATHODE_CATHODE") (pintype "passive"))
      (node (ref "IC2") (pin "41") (pinfunction "41_41") (pintype "power_in"))
      (node (ref "IC4") (pin "14") (pinfunction "VCC_14") (pintype "power_in"))
      (node (ref "IC5") (pin "41") (pinfunction "41_41") (pintype "power_in"))
      (node (ref "IC6") (pin "14") (pinfunction "VCC_14") (pintype "power_in"))
    )
    (net (code "99") (name "XT2IN_A") (class "Default")
      (node (ref "C6") (pin "P$2") (pinfunction "2_P$2") (pintype "passive"))
      (node (ref "IC2") (pin "45") (pinfunction "45_45") (pintype "bidirectional"))
      (node (ref "Q1") (pin "P$1") (pinfunction "1_P$1") (pintype "passive"))
    )
    (net (code "100") (name "XT2IN_B") (class "Default")
      (node (ref "C13") (pin "P$2") (pinfunction "2_P$2") (pintype "passive"))
      (node (ref "IC5") (pin "45") (pinfunction "45_45") (pintype "bidirectional"))
      (node (ref "Q2") (pin "P$1") (pinfunction "1_P$1") (pintype "passive"))
    )
    (net (code "101") (name "XT2OUT_A") (class "Default")
      (node (ref "C7") (pin "P$2") (pinfunction "2_P$2") (pintype "passive"))
      (node (ref "IC2") (pin "46") (pinfunction "46_46") (pintype "power_in"))
      (node (ref "Q1") (pin "P$2") (pinfunction "2_P$2") (pintype "passive"))
    )
    (net (code "102") (name "XT2OUT_B") (class "Default")
      (node (ref "C15") (pin "P$2") (pinfunction "2_P$2") (pintype "passive"))
      (node (ref "IC5") (pin "46") (pinfunction "46_46") (pintype "power_in"))
      (node (ref "Q2") (pin "P$2") (pinfunction "2_P$2") (pintype "passive"))
    )
    (net (code "103") (name "unconnected-(IC2-Pad2)") (class "Default")
      (node (ref "IC2") (pin "2") (pinfunction "2_2") (pintype "bidirectional"))
    )
    (net (code "104") (name "unconnected-(IC2-Pad3)") (class "Default")
      (node (ref "IC2") (pin "3") (pinfunction "3_3") (pintype "bidirectional"))
    )
    (net (code "105") (name "unconnected-(IC5-Pad2)") (class "Default")
      (node (ref "IC5") (pin "2") (pinfunction "2_2") (pintype "bidirectional"))
    )
    (net (code "106") (name "unconnected-(IC5-Pad3)") (class "Default")
      (node (ref "IC5") (pin "3") (pinfunction "3_3") (pintype "bidirectional"))
    )
    (net (code "107") (name "~{CE}_A") (class "Default")
      (node (ref "IC1") (pin "9") (pinfunction "~{CE}_9") (pintype "input"))
      (node (ref "IC2") (pin "32") (pinfunction "32_32") (pintype "bidirectional"))
    )
    (net (code "108") (name "~{CE}_B") (class "Default")
      (node (ref "IC3") (pin "9") (pinfunction "~{CE}_9") (pintype "input"))
      (node (ref "IC5") (pin "32") (pinfunction "32_32") (pintype "bidirectional"))
    )
    (net (code "109") (name "~{RE}_A") (class "Default")
      (node (ref "IC1") (pin "8") (pinfunction "~{RE}_8") (pintype "input"))
      (node (ref "IC2") (pin "35") (pinfunction "35_35") (pintype "bidirectional"))
    )
    (net (code "110") (name "~{RE}_B") (class "Default")
      (node (ref "IC3") (pin "8") (pinfunction "~{RE}_8") (pintype "input"))
      (node (ref "IC5") (pin "35") (pinfunction "35_35") (pintype "bidirectional"))
    )
    (net (code "111") (name "~{RST_A}") (class "Default")
      (node (ref "IC2") (pin "48") (pinfunction "48_48") (pintype "bidirectional"))
      (node (ref "R21") (pin "P$1") (pinfunction "1_P$1") (pintype "passive"))
      (node (ref "TP4") (pin "TP") (pinfunction "TP_TP") (pintype "input"))
    )
    (net (code "112") (name "~{RST_B}") (class "Default")
      (node (ref "IC5") (pin "48") (pinfunction "48_48") (pintype "bidirectional"))
      (node (ref "R13") (pin "P$1") (pinfunction "1_P$1") (pintype "passive"))
    )
    (net (code "113") (name "~{WE}_A") (class "Default")
      (node (ref "IC1") (pin "18") (pinfunction "~{WE}_18") (pintype "input"))
      (node (ref "IC2") (pin "30") (pinfunction "30_30") (pintype "bidirectional"))
    )
    (net (code "114") (name "~{WE}_B") (class "Default")
      (node (ref "IC3") (pin "18") (pinfunction "~{WE}_18") (pintype "input"))
      (node (ref "IC5") (pin "30") (pinfunction "30_30") (pintype "bidirectional"))
    )
    (net (code "115") (name "~{WP}_A") (class "Default")
      (node (ref "IC1") (pin "19") (pinfunction "~{WP}_19") (pintype "input"))
      (node (ref "IC2") (pin "29") (pinfunction "29_29") (pintype "bidirectional"))
    )
    (net (code "116") (name "~{WP}_B") (class "Default")
      (node (ref "IC3") (pin "19") (pinfunction "~{WP}_19") (pintype "input"))
      (node (ref "IC5") (pin "29") (pinfunction "29_29") (pintype "bidirectional"))
    )
  )
)
